# KeyInput_IJMEF.net
KiCad netlist of a schematic drawn in Altium Designer
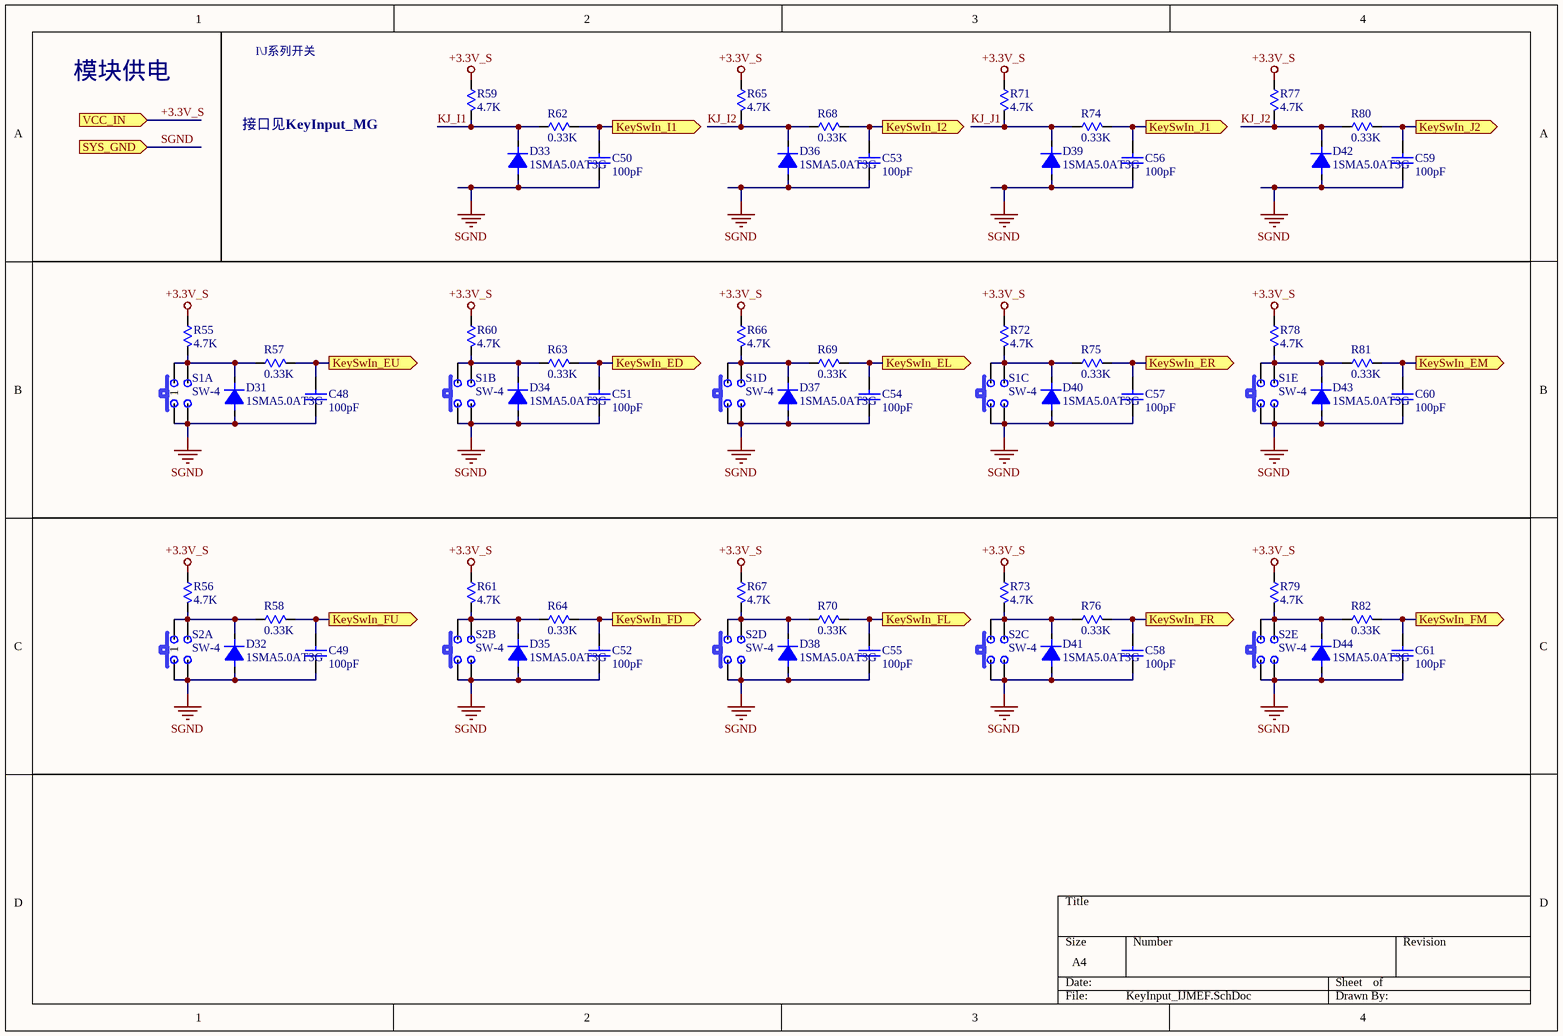
[diagram p0: KeyInput_IJMEF.SchDoc]

(export (version "E")
  (design (tool "Eeschema 10.0.6"))
  (components
    (comp (ref "C48")
      (value "100pF")
      (footprint "C0805")
      (description "Capacitor")
      (fields (field (name "PUBLISHER") "Altium Limited"))
      (libsource (lib "Miscellaneous Devices") (part "Cap"))
    )
    (comp (ref "C49")
      (value "100pF")
      (footprint "C0805")
      (description "Capacitor")
      (fields (field (name "PUBLISHER") "Altium Limited"))
      (libsource (lib "Miscellaneous Devices") (part "Cap"))
    )
    (comp (ref "C50")
      (value "100pF")
      (footprint "C0805")
      (description "Capacitor")
      (fields (field (name "PUBLISHER") "Altium Limited"))
      (libsource (lib "Miscellaneous Devices") (part "Cap"))
    )
    (comp (ref "C51")
      (value "100pF")
      (footprint "C0805")
      (description "Capacitor")
      (fields (field (name "PUBLISHER") "Altium Limited"))
      (libsource (lib "Miscellaneous Devices") (part "Cap"))
    )
    (comp (ref "C52")
      (value "100pF")
      (footprint "C0805")
      (description "Capacitor")
      (fields (field (name "PUBLISHER") "Altium Limited"))
      (libsource (lib "Miscellaneous Devices") (part "Cap"))
    )
    (comp (ref "C53")
      (value "100pF")
      (footprint "C0805")
      (description "Capacitor")
      (fields (field (name "PUBLISHER") "Altium Limited"))
      (libsource (lib "Miscellaneous Devices") (part "Cap"))
    )
    (comp (ref "C54")
      (value "100pF")
      (footprint "C0805")
      (description "Capacitor")
      (fields (field (name "PUBLISHER") "Altium Limited"))
      (libsource (lib "Miscellaneous Devices") (part "Cap"))
    )
    (comp (ref "C55")
      (value "100pF")
      (footprint "C0805")
      (description "Capacitor")
      (fields (field (name "PUBLISHER") "Altium Limited"))
      (libsource (lib "Miscellaneous Devices") (part "Cap"))
    )
    (comp (ref "C56")
      (value "100pF")
      (footprint "C0805")
      (description "Capacitor")
      (fields (field (name "PUBLISHER") "Altium Limited"))
      (libsource (lib "Miscellaneous Devices") (part "Cap"))
    )
    (comp (ref "C57")
      (value "100pF")
      (footprint "C0805")
      (description "Capacitor")
      (fields (field (name "PUBLISHER") "Altium Limited"))
      (libsource (lib "Miscellaneous Devices") (part "Cap"))
    )
    (comp (ref "C58")
      (value "100pF")
      (footprint "C0805")
      (description "Capacitor")
      (fields (field (name "PUBLISHER") "Altium Limited"))
      (libsource (lib "Miscellaneous Devices") (part "Cap"))
    )
    (comp (ref "C59")
      (value "100pF")
      (footprint "C0805")
      (description "Capacitor")
      (fields (field (name "PUBLISHER") "Altium Limited"))
      (libsource (lib "Miscellaneous Devices") (part "Cap"))
    )
    (comp (ref "C60")
      (value "100pF")
      (footprint "C0805")
      (description "Capacitor")
      (fields (field (name "PUBLISHER") "Altium Limited"))
      (libsource (lib "Miscellaneous Devices") (part "Cap"))
    )
    (comp (ref "C61")
      (value "100pF")
      (footprint "C0805")
      (description "Capacitor")
      (fields (field (name "PUBLISHER") "Altium Limited"))
      (libsource (lib "Miscellaneous Devices") (part "Cap"))
    )
    (comp (ref "D31")
      (value "1SMA5.0AT3G")
      (footprint "SMA")
      (description "Diode")
      (libsource (lib "*") (part "DIODE1"))
    )
    (comp (ref "D32")
      (value "1SMA5.0AT3G")
      (footprint "SMA")
      (description "Diode")
      (libsource (lib "*") (part "DIODE1"))
    )
    (comp (ref "D33")
      (value "1SMA5.0AT3G")
      (footprint "SMA")
      (description "Diode")
      (libsource (lib "*") (part "DIODE1"))
    )
    (comp (ref "D34")
      (value "1SMA5.0AT3G")
      (footprint "SMA")
      (description "Diode")
      (libsource (lib "*") (part "DIODE1"))
    )
    (comp (ref "D35")
      (value "1SMA5.0AT3G")
      (footprint "SMA")
      (description "Diode")
      (libsource (lib "*") (part "DIODE1"))
    )
    (comp (ref "D36")
      (value "1SMA5.0AT3G")
      (footprint "SMA")
      (description "Diode")
      (libsource (lib "*") (part "DIODE1"))
    )
    (comp (ref "D37")
      (value "1SMA5.0AT3G")
      (footprint "SMA")
      (description "Diode")
      (libsource (lib "*") (part "DIODE1"))
    )
    (comp (ref "D38")
      (value "1SMA5.0AT3G")
      (footprint "SMA")
      (description "Diode")
      (libsource (lib "*") (part "DIODE1"))
    )
    (comp (ref "D39")
      (value "1SMA5.0AT3G")
      (footprint "SMA")
      (description "Diode")
      (libsource (lib "*") (part "DIODE1"))
    )
    (comp (ref "D40")
      (value "1SMA5.0AT3G")
      (footprint "SMA")
      (description "Diode")
      (libsource (lib "*") (part "DIODE1"))
    )
    (comp (ref "D41")
      (value "1SMA5.0AT3G")
      (footprint "SMA")
      (description "Diode")
      (libsource (lib "*") (part "DIODE1"))
    )
    (comp (ref "D42")
      (value "1SMA5.0AT3G")
      (footprint "SMA")
      (description "Diode")
      (libsource (lib "*") (part "DIODE1"))
    )
    (comp (ref "D43")
      (value "1SMA5.0AT3G")
      (footprint "SMA")
      (description "Diode")
      (libsource (lib "*") (part "DIODE1"))
    )
    (comp (ref "D44")
      (value "1SMA5.0AT3G")
      (footprint "SMA")
      (description "Diode")
      (libsource (lib "*") (part "DIODE1"))
    )
    (comp (ref "R55")
      (value "4.7K")
      (footprint "R0805")
      (description "Resistor")
      (fields (field (name "PUBLISHER") "Altium Limited"))
      (libsource (lib "Passive Components Class") (part "RES"))
    )
    (comp (ref "R56")
      (value "4.7K")
      (footprint "R0805")
      (description "Resistor")
      (fields (field (name "PUBLISHER") "Altium Limited"))
      (libsource (lib "Passive Components Class") (part "RES"))
    )
    (comp (ref "R57")
      (value "0.33K")
      (footprint "R0805")
      (description "Resistor")
      (fields (field (name "PUBLISHER") "Altium Limited"))
      (libsource (lib "Passive Components Class") (part "RES"))
    )
    (comp (ref "R58")
      (value "0.33K")
      (footprint "R0805")
      (description "Resistor")
      (fields (field (name "PUBLISHER") "Altium Limited"))
      (libsource (lib "Passive Components Class") (part "RES"))
    )
    (comp (ref "R59")
      (value "4.7K")
      (footprint "R0805")
      (description "Resistor")
      (fields (field (name "PUBLISHER") "Altium Limited"))
      (libsource (lib "Passive Components Class") (part "RES"))
    )
    (comp (ref "R60")
      (value "4.7K")
      (footprint "R0805")
      (description "Resistor")
      (fields (field (name "PUBLISHER") "Altium Limited"))
      (libsource (lib "Passive Components Class") (part "RES"))
    )
    (comp (ref "R61")
      (value "4.7K")
      (footprint "R0805")
      (description "Resistor")
      (fields (field (name "PUBLISHER") "Altium Limited"))
      (libsource (lib "Passive Components Class") (part "RES"))
    )
    (comp (ref "R62")
      (value "0.33K")
      (footprint "R0805")
      (description "Resistor")
      (fields (field (name "PUBLISHER") "Altium Limited"))
      (libsource (lib "Passive Components Class") (part "RES"))
    )
    (comp (ref "R63")
      (value "0.33K")
      (footprint "R0805")
      (description "Resistor")
      (fields (field (name "PUBLISHER") "Altium Limited"))
      (libsource (lib "Passive Components Class") (part "RES"))
    )
    (comp (ref "R64")
      (value "0.33K")
      (footprint "R0805")
      (description "Resistor")
      (fields (field (name "PUBLISHER") "Altium Limited"))
      (libsource (lib "Passive Components Class") (part "RES"))
    )
    (comp (ref "R65")
      (value "4.7K")
      (footprint "R0805")
      (description "Resistor")
      (fields (field (name "PUBLISHER") "Altium Limited"))
      (libsource (lib "Passive Components Class") (part "RES"))
    )
    (comp (ref "R66")
      (value "4.7K")
      (footprint "R0805")
      (description "Resistor")
      (fields (field (name "PUBLISHER") "Altium Limited"))
      (libsource (lib "Passive Components Class") (part "RES"))
    )
    (comp (ref "R67")
      (value "4.7K")
      (footprint "R0805")
      (description "Resistor")
      (fields (field (name "PUBLISHER") "Altium Limited"))
      (libsource (lib "Passive Components Class") (part "RES"))
    )
    (comp (ref "R68")
      (value "0.33K")
      (footprint "R0805")
      (description "Resistor")
      (fields (field (name "PUBLISHER") "Altium Limited"))
      (libsource (lib "Passive Components Class") (part "RES"))
    )
    (comp (ref "R69")
      (value "0.33K")
      (footprint "R0805")
      (description "Resistor")
      (fields (field (name "PUBLISHER") "Altium Limited"))
      (libsource (lib "Passive Components Class") (part "RES"))
    )
    (comp (ref "R70")
      (value "0.33K")
      (footprint "R0805")
      (description "Resistor")
      (fields (field (name "PUBLISHER") "Altium Limited"))
      (libsource (lib "Passive Components Class") (part "RES"))
    )
    (comp (ref "R71")
      (value "4.7K")
      (footprint "R0805")
      (description "Resistor")
      (fields (field (name "PUBLISHER") "Altium Limited"))
      (libsource (lib "Passive Components Class") (part "RES"))
    )
    (comp (ref "R72")
      (value "4.7K")
      (footprint "R0805")
      (description "Resistor")
      (fields (field (name "PUBLISHER") "Altium Limited"))
      (libsource (lib "Passive Components Class") (part "RES"))
    )
    (comp (ref "R73")
      (value "4.7K")
      (footprint "R0805")
      (description "Resistor")
      (fields (field (name "PUBLISHER") "Altium Limited"))
      (libsource (lib "Passive Components Class") (part "RES"))
    )
    (comp (ref "R74")
      (value "0.33K")
      (footprint "R0805")
      (description "Resistor")
      (fields (field (name "PUBLISHER") "Altium Limited"))
      (libsource (lib "Passive Components Class") (part "RES"))
    )
    (comp (ref "R75")
      (value "0.33K")
      (footprint "R0805")
      (description "Resistor")
      (fields (field (name "PUBLISHER") "Altium Limited"))
      (libsource (lib "Passive Components Class") (part "RES"))
    )
    (comp (ref "R76")
      (value "0.33K")
      (footprint "R0805")
      (description "Resistor")
      (fields (field (name "PUBLISHER") "Altium Limited"))
      (libsource (lib "Passive Components Class") (part "RES"))
    )
    (comp (ref "R77")
      (value "4.7K")
      (footprint "R0805")
      (description "Resistor")
      (fields (field (name "PUBLISHER") "Altium Limited"))
      (libsource (lib "Passive Components Class") (part "RES"))
    )
    (comp (ref "R78")
      (value "4.7K")
      (footprint "R0805")
      (description "Resistor")
      (fields (field (name "PUBLISHER") "Altium Limited"))
      (libsource (lib "Passive Components Class") (part "RES"))
    )
    (comp (ref "R79")
      (value "4.7K")
      (footprint "R0805")
      (description "Resistor")
      (fields (field (name "PUBLISHER") "Altium Limited"))
      (libsource (lib "Passive Components Class") (part "RES"))
    )
    (comp (ref "R80")
      (value "0.33K")
      (footprint "R0805")
      (description "Resistor")
      (fields (field (name "PUBLISHER") "Altium Limited"))
      (libsource (lib "Passive Components Class") (part "RES"))
    )
    (comp (ref "R81")
      (value "0.33K")
      (footprint "R0805")
      (description "Resistor")
      (fields (field (name "PUBLISHER") "Altium Limited"))
      (libsource (lib "Passive Components Class") (part "RES"))
    )
    (comp (ref "R82")
      (value "0.33K")
      (footprint "R0805")
      (description "Resistor")
      (fields (field (name "PUBLISHER") "Altium Limited"))
      (libsource (lib "Passive Components Class") (part "RES"))
    )
    (comp (ref "S1")
      (value "SW-4")
      (footprint "SW-MEC-5")
      (libsource (lib "Passive Components Class") (part "SW-4"))
    )
    (comp (ref "S2")
      (value "SW-4")
      (footprint "SW-MEC-5")
      (libsource (lib "Passive Components Class") (part "SW-4"))
    )
  )
  (nets
    (net (code "1") (name "+3.3V_S") (class "Default")
      (node (ref "R55") (pin "2") (pinfunction "2_2") (pintype "passive"))
      (node (ref "R56") (pin "2") (pinfunction "2_2") (pintype "passive"))
      (node (ref "R59") (pin "2") (pinfunction "2_2") (pintype "passive"))
      (node (ref "R60") (pin "2") (pinfunction "2_2") (pintype "passive"))
      (node (ref "R61") (pin "2") (pinfunction "2_2") (pintype "passive"))
      (node (ref "R65") (pin "2") (pinfunction "2_2") (pintype "passive"))
      (node (ref "R66") (pin "2") (pinfunction "2_2") (pintype "passive"))
      (node (ref "R67") (pin "2") (pinfunction "2_2") (pintype "passive"))
      (node (ref "R71") (pin "2") (pinfunction "2_2") (pintype "passive"))
      (node (ref "R72") (pin "2") (pinfunction "2_2") (pintype "passive"))
      (node (ref "R73") (pin "2") (pinfunction "2_2") (pintype "passive"))
      (node (ref "R77") (pin "2") (pinfunction "2_2") (pintype "passive"))
      (node (ref "R78") (pin "2") (pinfunction "2_2") (pintype "passive"))
      (node (ref "R79") (pin "2") (pinfunction "2_2") (pintype "passive"))
    )
    (net (code "2") (name "/KJ_I1") (class "Default")
      (node (ref "D33") (pin "2") (pinfunction "K_2") (pintype "passive"))
      (node (ref "R59") (pin "1") (pinfunction "1_1") (pintype "passive"))
      (node (ref "R62") (pin "2") (pinfunction "2_2") (pintype "passive"))
    )
    (net (code "3") (name "/KJ_I2") (class "Default")
      (node (ref "D36") (pin "2") (pinfunction "K_2") (pintype "passive"))
      (node (ref "R65") (pin "1") (pinfunction "1_1") (pintype "passive"))
      (node (ref "R68") (pin "2") (pinfunction "2_2") (pintype "passive"))
    )
    (net (code "4") (name "/KJ_J1") (class "Default")
      (node (ref "D39") (pin "2") (pinfunction "K_2") (pintype "passive"))
      (node (ref "R71") (pin "1") (pinfunction "1_1") (pintype "passive"))
      (node (ref "R74") (pin "2") (pinfunction "2_2") (pintype "passive"))
    )
    (net (code "5") (name "/KJ_J2") (class "Default")
      (node (ref "D42") (pin "2") (pinfunction "K_2") (pintype "passive"))
      (node (ref "R77") (pin "1") (pinfunction "1_1") (pintype "passive"))
      (node (ref "R80") (pin "2") (pinfunction "2_2") (pintype "passive"))
    )
    (net (code "6") (name "/KeySwIn_ED") (class "Default")
      (node (ref "C51") (pin "1") (pinfunction "1_1") (pintype "passive"))
      (node (ref "R63") (pin "1") (pinfunction "1_1") (pintype "passive"))
    )
    (net (code "7") (name "/KeySwIn_EL") (class "Default")
      (node (ref "C54") (pin "1") (pinfunction "1_1") (pintype "passive"))
      (node (ref "R69") (pin "1") (pinfunction "1_1") (pintype "passive"))
    )
    (net (code "8") (name "/KeySwIn_EM") (class "Default")
      (node (ref "C60") (pin "1") (pinfunction "1_1") (pintype "passive"))
      (node (ref "R81") (pin "1") (pinfunction "1_1") (pintype "passive"))
    )
    (net (code "9") (name "/KeySwIn_ER") (class "Default")
      (node (ref "C57") (pin "1") (pinfunction "1_1") (pintype "passive"))
      (node (ref "R75") (pin "1") (pinfunction "1_1") (pintype "passive"))
    )
    (net (code "10") (name "/KeySwIn_EU") (class "Default")
      (node (ref "C48") (pin "1") (pinfunction "1_1") (pintype "passive"))
      (node (ref "R57") (pin "1") (pinfunction "1_1") (pintype "passive"))
    )
    (net (code "11") (name "/KeySwIn_FD") (class "Default")
      (node (ref "C52") (pin "1") (pinfunction "1_1") (pintype "passive"))
      (node (ref "R64") (pin "1") (pinfunction "1_1") (pintype "passive"))
    )
    (net (code "12") (name "/KeySwIn_FL") (class "Default")
      (node (ref "C55") (pin "1") (pinfunction "1_1") (pintype "passive"))
      (node (ref "R70") (pin "1") (pinfunction "1_1") (pintype "passive"))
    )
    (net (code "13") (name "/KeySwIn_FM") (class "Default")
      (node (ref "C61") (pin "1") (pinfunction "1_1") (pintype "passive"))
      (node (ref "R82") (pin "1") (pinfunction "1_1") (pintype "passive"))
    )
    (net (code "14") (name "/KeySwIn_FR") (class "Default")
      (node (ref "C58") (pin "1") (pinfunction "1_1") (pintype "passive"))
      (node (ref "R76") (pin "1") (pinfunction "1_1") (pintype "passive"))
    )
    (net (code "15") (name "/KeySwIn_FU") (class "Default")
      (node (ref "C49") (pin "1") (pinfunction "1_1") (pintype "passive"))
      (node (ref "R58") (pin "1") (pinfunction "1_1") (pintype "passive"))
    )
    (net (code "16") (name "/KeySwIn_I1") (class "Default")
      (node (ref "C50") (pin "1") (pinfunction "1_1") (pintype "passive"))
      (node (ref "R62") (pin "1") (pinfunction "1_1") (pintype "passive"))
    )
    (net (code "17") (name "/KeySwIn_I2") (class "Default")
      (node (ref "C53") (pin "1") (pinfunction "1_1") (pintype "passive"))
      (node (ref "R68") (pin "1") (pinfunction "1_1") (pintype "passive"))
    )
    (net (code "18") (name "/KeySwIn_J1") (class "Default")
      (node (ref "C56") (pin "1") (pinfunction "1_1") (pintype "passive"))
      (node (ref "R74") (pin "1") (pinfunction "1_1") (pintype "passive"))
    )
    (net (code "19") (name "/KeySwIn_J2") (class "Default")
      (node (ref "C59") (pin "1") (pinfunction "1_1") (pintype "passive"))
      (node (ref "R80") (pin "1") (pinfunction "1_1") (pintype "passive"))
    )
    (net (code "20") (name "Net-(D31-K)") (class "Default")
      (node (ref "D31") (pin "2") (pinfunction "K_2") (pintype "passive"))
      (node (ref "R55") (pin "1") (pinfunction "1_1") (pintype "passive"))
      (node (ref "R57") (pin "2") (pinfunction "2_2") (pintype "passive"))
      (node (ref "S1") (pin "2") (pintype "passive"))
    )
    (net (code "21") (name "Net-(D32-K)") (class "Default")
      (node (ref "D32") (pin "2") (pinfunction "K_2") (pintype "passive"))
      (node (ref "R56") (pin "1") (pinfunction "1_1") (pintype "passive"))
      (node (ref "R58") (pin "2") (pinfunction "2_2") (pintype "passive"))
      (node (ref "S2") (pin "2") (pintype "passive"))
    )
    (net (code "22") (name "Net-(D34-K)") (class "Default")
      (node (ref "D34") (pin "2") (pinfunction "K_2") (pintype "passive"))
      (node (ref "R60") (pin "1") (pinfunction "1_1") (pintype "passive"))
      (node (ref "R63") (pin "2") (pinfunction "2_2") (pintype "passive"))
      (node (ref "S1") (pin "4") (pintype "passive"))
    )
    (net (code "23") (name "Net-(D35-K)") (class "Default")
      (node (ref "D35") (pin "2") (pinfunction "K_2") (pintype "passive"))
      (node (ref "R61") (pin "1") (pinfunction "1_1") (pintype "passive"))
      (node (ref "R64") (pin "2") (pinfunction "2_2") (pintype "passive"))
      (node (ref "S2") (pin "4") (pintype "passive"))
    )
    (net (code "24") (name "Net-(D37-K)") (class "Default")
      (node (ref "D37") (pin "2") (pinfunction "K_2") (pintype "passive"))
      (node (ref "R66") (pin "1") (pinfunction "1_1") (pintype "passive"))
      (node (ref "R69") (pin "2") (pinfunction "2_2") (pintype "passive"))
      (node (ref "S1") (pin "8") (pintype "passive"))
    )
    (net (code "25") (name "Net-(D38-K)") (class "Default")
      (node (ref "D38") (pin "2") (pinfunction "K_2") (pintype "passive"))
      (node (ref "R67") (pin "1") (pinfunction "1_1") (pintype "passive"))
      (node (ref "R70") (pin "2") (pinfunction "2_2") (pintype "passive"))
      (node (ref "S2") (pin "8") (pintype "passive"))
    )
    (net (code "26") (name "Net-(D40-K)") (class "Default")
      (node (ref "D40") (pin "2") (pinfunction "K_2") (pintype "passive"))
      (node (ref "R72") (pin "1") (pinfunction "1_1") (pintype "passive"))
      (node (ref "R75") (pin "2") (pinfunction "2_2") (pintype "passive"))
      (node (ref "S1") (pin "6") (pintype "passive"))
    )
    (net (code "27") (name "Net-(D41-K)") (class "Default")
      (node (ref "D41") (pin "2") (pinfunction "K_2") (pintype "passive"))
      (node (ref "R73") (pin "1") (pinfunction "1_1") (pintype "passive"))
      (node (ref "R76") (pin "2") (pinfunction "2_2") (pintype "passive"))
      (node (ref "S2") (pin "6") (pintype "passive"))
    )
    (net (code "28") (name "Net-(D43-K)") (class "Default")
      (node (ref "D43") (pin "2") (pinfunction "K_2") (pintype "passive"))
      (node (ref "R78") (pin "1") (pinfunction "1_1") (pintype "passive"))
      (node (ref "R81") (pin "2") (pinfunction "2_2") (pintype "passive"))
      (node (ref "S1") (pin "10") (pintype "passive"))
    )
    (net (code "29") (name "Net-(D44-K)") (class "Default")
      (node (ref "D44") (pin "2") (pinfunction "K_2") (pintype "passive"))
      (node (ref "R79") (pin "1") (pinfunction "1_1") (pintype "passive"))
      (node (ref "R82") (pin "2") (pinfunction "2_2") (pintype "passive"))
      (node (ref "S2") (pin "10") (pintype "passive"))
    )
    (net (code "30") (name "SGND") (class "Default")
      (node (ref "C48") (pin "2") (pinfunction "2_2") (pintype "passive"))
      (node (ref "C49") (pin "2") (pinfunction "2_2") (pintype "passive"))
      (node (ref "C50") (pin "2") (pinfunction "2_2") (pintype "passive"))
      (node (ref "C51") (pin "2") (pinfunction "2_2") (pintype "passive"))
      (node (ref "C52") (pin "2") (pinfunction "2_2") (pintype "passive"))
      (node (ref "C53") (pin "2") (pinfunction "2_2") (pintype "passive"))
      (node (ref "C54") (pin "2") (pinfunction "2_2") (pintype "passive"))
      (node (ref "C55") (pin "2") (pinfunction "2_2") (pintype "passive"))
      (node (ref "C56") (pin "2") (pinfunction "2_2") (pintype "passive"))
      (node (ref "C57") (pin "2") (pinfunction "2_2") (pintype "passive"))
      (node (ref "C58") (pin "2") (pinfunction "2_2") (pintype "passive"))
      (node (ref "C59") (pin "2") (pinfunction "2_2") (pintype "passive"))
      (node (ref "C60") (pin "2") (pinfunction "2_2") (pintype "passive"))
      (node (ref "C61") (pin "2") (pinfunction "2_2") (pintype "passive"))
      (node (ref "D31") (pin "1") (pinfunction "A_1") (pintype "passive"))
      (node (ref "D32") (pin "1") (pinfunction "A_1") (pintype "passive"))
      (node (ref "D33") (pin "1") (pinfunction "A_1") (pintype "passive"))
      (node (ref "D34") (pin "1") (pinfunction "A_1") (pintype "passive"))
      (node (ref "D35") (pin "1") (pinfunction "A_1") (pintype "passive"))
      (node (ref "D36") (pin "1") (pinfunction "A_1") (pintype "passive"))
      (node (ref "D37") (pin "1") (pinfunction "A_1") (pintype "passive"))
      (node (ref "D38") (pin "1") (pinfunction "A_1") (pintype "passive"))
      (node (ref "D39") (pin "1") (pinfunction "A_1") (pintype "passive"))
      (node (ref "D40") (pin "1") (pinfunction "A_1") (pintype "passive"))
      (node (ref "D41") (pin "1") (pinfunction "A_1") (pintype "passive"))
      (node (ref "D42") (pin "1") (pinfunction "A_1") (pintype "passive"))
      (node (ref "D43") (pin "1") (pinfunction "A_1") (pintype "passive"))
      (node (ref "D44") (pin "1") (pinfunction "A_1") (pintype "passive"))
      (node (ref "S1") (pin "1") (pintype "passive"))
      (node (ref "S1") (pin "3") (pintype "passive"))
      (node (ref "S1") (pin "5") (pintype "passive"))
      (node (ref "S1") (pin "7") (pintype "passive"))
      (node (ref "S1") (pin "9") (pintype "passive"))
      (node (ref "S2") (pin "1") (pinfunction "1_1") (pintype "passive"))
      (node (ref "S2") (pin "3") (pintype "passive"))
      (node (ref "S2") (pin "5") (pintype "passive"))
      (node (ref "S2") (pin "7") (pintype "passive"))
      (node (ref "S2") (pin "9") (pintype "passive"))
    )
  )
)
